# 5_AUX.net
KiCad netlist of a schematic drawn in Altium Designer
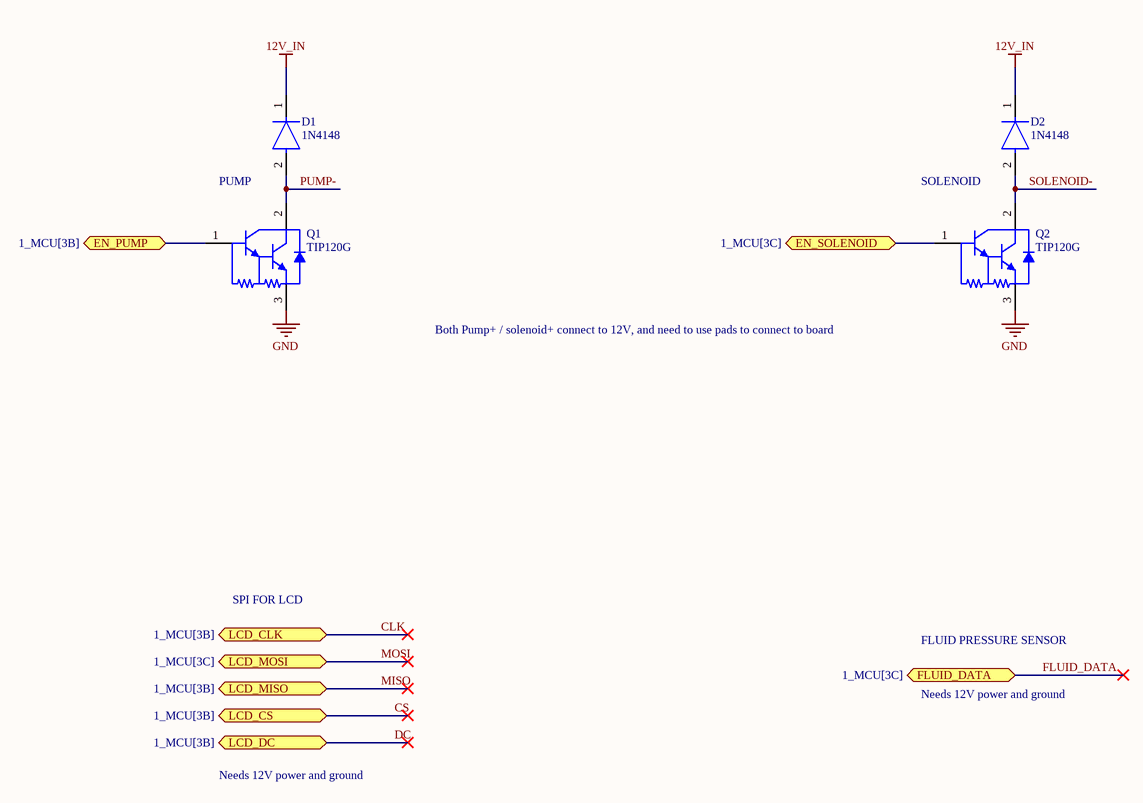
[diagram p0: 5_AUX.SchDoc]

(export (version "E")
  (design (tool "Eeschema 10.0.6"))
  (components
    (comp (ref "D1")
      (value "1N4148")
      (footprint "FP-017AG-MFG")
      (description "DIODE GEN PURP 100V 200MA DO35")
      (fields (field (name "VOLTAGE") "100V"))
      (libsource (lib "Altium Content Vault") (part "d7152d700b627762746794eb795d46e"))
    )
    (comp (ref "D2")
      (value "1N4148")
      (footprint "FP-017AG-MFG")
      (description "DIODE GEN PURP 100V 200MA DO35")
      (fields (field (name "VOLTAGE") "100V"))
      (libsource (lib "Altium Content Vault") (part "d7152d700b627762746794eb795d46e"))
    )
    (comp (ref "Q1")
      (value "TIP120G")
      (footprint "ONSC-TO-220-3-221A-09")
      (description "Plastic Medium-Power, Complementary Silicon Transistor, 3-Pin TO-220, Pb-Free, Tube")
      (fields (field (name "MANUFACTURER") "On Semiconductor"))
      (libsource (lib "Altium Content Vault") (part "ONSC-DT-NPN-B1C2E3-3_A"))
    )
    (comp (ref "Q2")
      (value "TIP120G")
      (footprint "ONSC-TO-220-3-221A-09")
      (description "Plastic Medium-Power, Complementary Silicon Transistor, 3-Pin TO-220, Pb-Free, Tube")
      (fields (field (name "MANUFACTURER") "On Semiconductor"))
      (libsource (lib "Altium Content Vault") (part "ONSC-DT-NPN-B1C2E3-3_A"))
    )
  )
  (nets
    (net (code "4") (name "/EN_PUMP") (class "Default")
      (node (ref "Q1") (pin "1") (pinfunction "B_1") (pintype "passive"))
    )
    (net (code "5") (name "/EN_SOLENOID") (class "Default")
      (node (ref "Q2") (pin "1") (pinfunction "B_1") (pintype "passive"))
    )
    (net (code "9") (name "/PUMP-") (class "Default")
      (node (ref "D1") (pin "2") (pinfunction "A_2") (pintype "passive"))
      (node (ref "Q1") (pin "2") (pinfunction "C_2") (pintype "passive"))
    )
    (net (code "10") (name "/SOLENOID-") (class "Default")
      (node (ref "D2") (pin "2") (pinfunction "A_2") (pintype "passive"))
      (node (ref "Q2") (pin "2") (pinfunction "C_2") (pintype "passive"))
    )
    (net (code "11") (name "12V_IN") (class "Default")
      (node (ref "D1") (pin "1") (pinfunction "C_1") (pintype "passive"))
      (node (ref "D2") (pin "1") (pinfunction "C_1") (pintype "passive"))
    )
    (net (code "12") (name "GND") (class "Default")
      (node (ref "Q1") (pin "3") (pinfunction "E_3") (pintype "passive"))
      (node (ref "Q2") (pin "3") (pinfunction "E_3") (pintype "passive"))
    )
  )
)
